# Hmi.net
KiCad netlist of a schematic drawn in Altium Designer
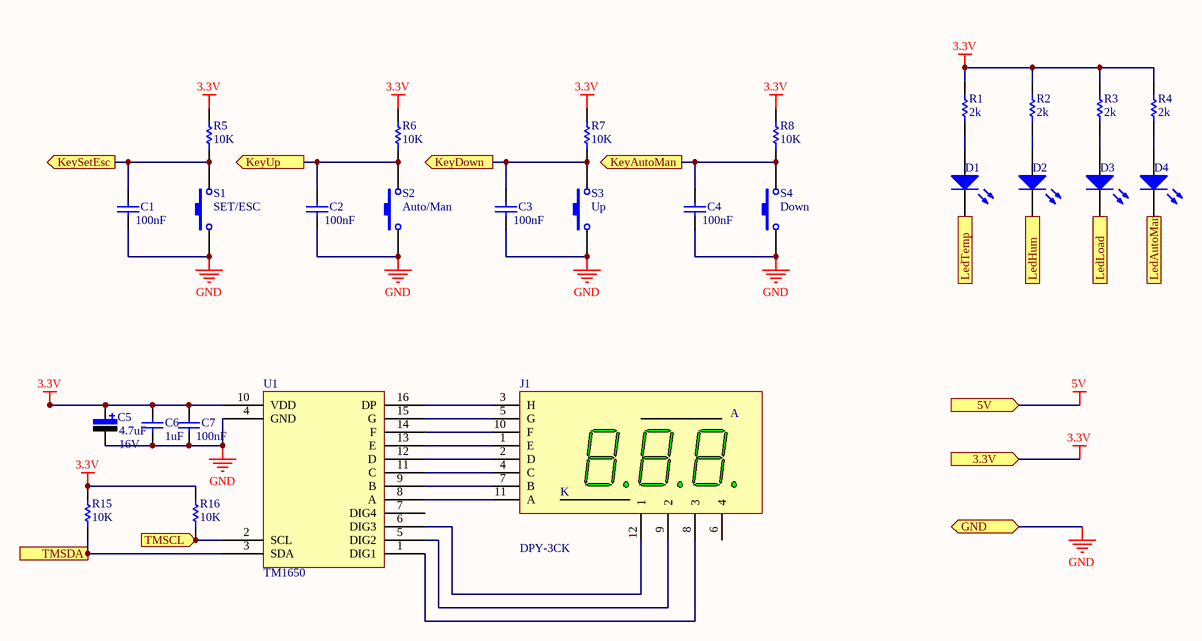
[diagram p0: Hmi.SchDoc]

(export (version "E")
  (design (tool "Eeschema 10.0.6"))
  (components
    (comp (ref "C1")
      (value "100nF (104) 10% 50V")
      (footprint "0603_C")
      (description "贴片电容")
      (fields (field (name "ALTIUM_UNNAMED_1") "100nF"))
      (libsource (lib "Miscellaneous Devices LC") (part "0603 100nF (104) 10% 50V"))
    )
    (comp (ref "C2")
      (value "100nF (104) 10% 50V")
      (footprint "0603_C")
      (description "贴片电容")
      (fields (field (name "ALTIUM_UNNAMED_1") "100nF"))
      (libsource (lib "Miscellaneous Devices LC") (part "0603 100nF (104) 10% 50V"))
    )
    (comp (ref "C3")
      (value "100nF (104) 10% 50V")
      (footprint "0603_C")
      (description "贴片电容")
      (fields (field (name "ALTIUM_UNNAMED_1") "100nF"))
      (libsource (lib "Miscellaneous Devices LC") (part "0603 100nF (104) 10% 50V"))
    )
    (comp (ref "C4")
      (value "100nF (104) 10% 50V")
      (footprint "0603_C")
      (description "贴片电容")
      (fields (field (name "ALTIUM_UNNAMED_1") "100nF"))
      (libsource (lib "Miscellaneous Devices LC") (part "0603 100nF (104) 10% 50V"))
    )
    (comp (ref "C5")
      (value "4.7uF")
      (footprint "CAP-1206")
      (description "4.7uF/16V钽电容")
      (fields
        (field (name "VOL") "16V")
        (field (name "Comment") "4.7uF/16V")
        (field (name "PUBLISHER") "Altium Limited")
      )
      (libsource (lib "fszhang") (part "Cap Pol"))
    )
    (comp (ref "C6")
      (value "1uF (105) 10% 50V")
      (footprint "0603_C")
      (description "贴片电容")
      (fields (field (name "ALTIUM_UNNAMED_1") "1uF"))
      (libsource (lib "Miscellaneous Devices LC") (part "0603 1uF (105) 10% 50V"))
    )
    (comp (ref "C7")
      (value "100nF (104) 10% 50V")
      (footprint "0603_C")
      (description "贴片电容")
      (fields (field (name "ALTIUM_UNNAMED_1") "100nF"))
      (libsource (lib "Miscellaneous Devices LC") (part "0603 100nF (104) 10% 50V"))
    )
    (comp (ref "D1")
      (value "LED")
      (footprint "LED(小)")
      (description "Typical INFRARED GaAs LED")
      (fields (field (name "PUBLISHER") "Altium Limited"))
      (libsource (lib "Miscellaneous Devices") (part "LED0"))
    )
    (comp (ref "D2")
      (value "LED")
      (footprint "LED(小)")
      (description "Typical INFRARED GaAs LED")
      (fields (field (name "PUBLISHER") "Altium Limited"))
      (libsource (lib "Miscellaneous Devices") (part "LED0"))
    )
    (comp (ref "D3")
      (value "LED")
      (footprint "LED(小)")
      (description "Typical INFRARED GaAs LED")
      (fields (field (name "PUBLISHER") "Altium Limited"))
      (libsource (lib "Miscellaneous Devices") (part "LED0"))
    )
    (comp (ref "D4")
      (value "LED")
      (footprint "LED(小)")
      (description "Typical INFRARED GaAs LED")
      (fields (field (name "PUBLISHER") "Altium Limited"))
      (libsource (lib "Miscellaneous Devices") (part "LED0"))
    )
    (comp (ref "J1")
      (value "DPY-3CK")
      (footprint "DYP-3BIT_2.8")
      (description "共阴3位数码管")
      (libsource (lib "PowerDisplay") (part "DPY-3CK_1"))
    )
    (comp (ref "R1")
      (value "2k")
      (footprint "0603_R")
      (description "2k/±10%")
      (libsource (lib "Free Documents") (part "RES1"))
    )
    (comp (ref "R2")
      (value "2k")
      (footprint "0603_R")
      (description "2k/±10%")
      (libsource (lib "Free Documents") (part "RES1"))
    )
    (comp (ref "R3")
      (value "2k")
      (footprint "0603_R")
      (description "2k/±10%")
      (libsource (lib "Free Documents") (part "RES1"))
    )
    (comp (ref "R4")
      (value "2k")
      (footprint "0603_R")
      (description "2k/±10%")
      (libsource (lib "Free Documents") (part "RES1"))
    )
    (comp (ref "R5")
      (value "10K")
      (footprint "0603_R")
      (description "10K/±10%")
      (libsource (lib "Free Documents") (part "RES1"))
    )
    (comp (ref "R6")
      (value "10K")
      (footprint "0603_R")
      (description "10K/±10%")
      (libsource (lib "Free Documents") (part "RES1"))
    )
    (comp (ref "R7")
      (value "10K")
      (footprint "0603_R")
      (description "10K/±10%")
      (libsource (lib "Free Documents") (part "RES1"))
    )
    (comp (ref "R8")
      (value "10K")
      (footprint "0603_R")
      (description "10K/±10%")
      (libsource (lib "Free Documents") (part "RES1"))
    )
    (comp (ref "R15")
      (value "10K")
      (footprint "0603_R")
      (description "10K/±10%")
      (libsource (lib "Free Documents") (part "RES1"))
    )
    (comp (ref "R16")
      (value "10K")
      (footprint "0603_R")
      (description "10K/±10%")
      (libsource (lib "Free Documents") (part "RES1"))
    )
    (comp (ref "S1")
      (value "SET/ESC")
      (footprint "Switch_4_6*6")
      (description "6*6*5四脚直插轻触开关")
      (libsource (lib "Free Documents") (part "SW-PB"))
    )
    (comp (ref "S2")
      (value "Auto/Man")
      (footprint "Switch_4_6*6")
      (description "6*6*5四脚直插轻触开关")
      (libsource (lib "Free Documents") (part "SW-PB"))
    )
    (comp (ref "S3")
      (value "Up")
      (footprint "Switch_4_6*6")
      (description "6*6*5四脚直插轻触开关")
      (libsource (lib "Free Documents") (part "SW-PB"))
    )
    (comp (ref "S4")
      (value "Down")
      (footprint "Switch_4_6*6")
      (description "6*6*5四脚直插轻触开关")
      (libsource (lib "Free Documents") (part "SW-PB"))
    )
    (comp (ref "U1")
      (value "TM1650")
      (footprint "Miscellaneous Devices LC:SOIC-16_150mil")
      (libsource (lib "LifeTestDevice") (part "TM1650"))
    )
  )
  (nets
    (net (code "1") (name "/KeyAutoMan") (class "Default")
      (node (ref "C4") (pin "2") (pinfunction "2_2") (pintype "passive"))
      (node (ref "R8") (pin "1") (pinfunction "1_1") (pintype "passive"))
      (node (ref "S4") (pin "2") (pinfunction "2_2") (pintype "passive"))
    )
    (net (code "2") (name "/KeyDown") (class "Default")
      (node (ref "C3") (pin "2") (pinfunction "2_2") (pintype "passive"))
      (node (ref "R7") (pin "1") (pinfunction "1_1") (pintype "passive"))
      (node (ref "S3") (pin "2") (pinfunction "2_2") (pintype "passive"))
    )
    (net (code "3") (name "/KeySetEsc") (class "Default")
      (node (ref "C1") (pin "2") (pinfunction "2_2") (pintype "passive"))
      (node (ref "R5") (pin "1") (pinfunction "1_1") (pintype "passive"))
      (node (ref "S1") (pin "2") (pinfunction "2_2") (pintype "passive"))
    )
    (net (code "4") (name "/KeyUp") (class "Default")
      (node (ref "C2") (pin "2") (pinfunction "2_2") (pintype "passive"))
      (node (ref "R6") (pin "1") (pinfunction "1_1") (pintype "passive"))
      (node (ref "S2") (pin "2") (pinfunction "2_2") (pintype "passive"))
    )
    (net (code "5") (name "/LedAutoMan") (class "Default")
      (node (ref "D4") (pin "2") (pinfunction "K_2") (pintype "passive"))
    )
    (net (code "6") (name "/LedHum") (class "Default")
      (node (ref "D2") (pin "2") (pinfunction "K_2") (pintype "passive"))
    )
    (net (code "7") (name "/LedLoad") (class "Default")
      (node (ref "D3") (pin "2") (pinfunction "K_2") (pintype "passive"))
    )
    (net (code "8") (name "/LedTemp") (class "Default")
      (node (ref "D1") (pin "2") (pinfunction "K_2") (pintype "passive"))
    )
    (net (code "9") (name "/TMSCL") (class "Default")
      (node (ref "R16") (pin "1") (pinfunction "1_1") (pintype "passive"))
      (node (ref "U1") (pin "2") (pinfunction "SCL_2") (pintype "passive"))
    )
    (net (code "10") (name "/TMSDA") (class "Default")
      (node (ref "R15") (pin "1") (pinfunction "1_1") (pintype "passive"))
      (node (ref "U1") (pin "3") (pinfunction "SDA_3") (pintype "passive"))
    )
    (net (code "11") (name "3.3V") (class "Default")
      (node (ref "C5") (pin "1") (pinfunction "1_1") (pintype "passive"))
      (node (ref "C6") (pin "2") (pinfunction "2_2") (pintype "passive"))
      (node (ref "C7") (pin "2") (pinfunction "2_2") (pintype "passive"))
      (node (ref "R1") (pin "1") (pinfunction "1_1") (pintype "passive"))
      (node (ref "R15") (pin "2") (pinfunction "2_2") (pintype "passive"))
      (node (ref "R16") (pin "2") (pinfunction "2_2") (pintype "passive"))
      (node (ref "R2") (pin "1") (pinfunction "1_1") (pintype "passive"))
      (node (ref "R3") (pin "1") (pinfunction "1_1") (pintype "passive"))
      (node (ref "R4") (pin "1") (pinfunction "1_1") (pintype "passive"))
      (node (ref "R5") (pin "2") (pinfunction "2_2") (pintype "passive"))
      (node (ref "R6") (pin "2") (pinfunction "2_2") (pintype "passive"))
      (node (ref "R7") (pin "2") (pinfunction "2_2") (pintype "passive"))
      (node (ref "R8") (pin "2") (pinfunction "2_2") (pintype "passive"))
      (node (ref "U1") (pin "10") (pinfunction "VDD_10") (pintype "passive"))
    )
    (net (code "13") (name "GND") (class "Default")
      (node (ref "C1") (pin "1") (pinfunction "1_1") (pintype "passive"))
      (node (ref "C2") (pin "1") (pinfunction "1_1") (pintype "passive"))
      (node (ref "C3") (pin "1") (pinfunction "1_1") (pintype "passive"))
      (node (ref "C4") (pin "1") (pinfunction "1_1") (pintype "passive"))
      (node (ref "C5") (pin "2") (pinfunction "2_2") (pintype "passive"))
      (node (ref "C6") (pin "1") (pinfunction "1_1") (pintype "passive"))
      (node (ref "C7") (pin "1") (pinfunction "1_1") (pintype "passive"))
      (node (ref "S1") (pin "1") (pinfunction "1_1") (pintype "passive"))
      (node (ref "S2") (pin "1") (pinfunction "1_1") (pintype "passive"))
      (node (ref "S3") (pin "1") (pinfunction "1_1") (pintype "passive"))
      (node (ref "S4") (pin "1") (pinfunction "1_1") (pintype "passive"))
      (node (ref "U1") (pin "4") (pinfunction "GND_4") (pintype "passive"))
    )
    (net (code "14") (name "Net-(D1-A)") (class "Default")
      (node (ref "D1") (pin "1") (pinfunction "A_1") (pintype "passive"))
      (node (ref "R1") (pin "2") (pinfunction "2_2") (pintype "passive"))
    )
    (net (code "15") (name "Net-(D2-A)") (class "Default")
      (node (ref "D2") (pin "1") (pinfunction "A_1") (pintype "passive"))
      (node (ref "R2") (pin "2") (pinfunction "2_2") (pintype "passive"))
    )
    (net (code "16") (name "Net-(D3-A)") (class "Default")
      (node (ref "D3") (pin "1") (pinfunction "A_1") (pintype "passive"))
      (node (ref "R3") (pin "2") (pinfunction "2_2") (pintype "passive"))
    )
    (net (code "17") (name "Net-(D4-A)") (class "Default")
      (node (ref "D4") (pin "1") (pinfunction "A_1") (pintype "passive"))
      (node (ref "R4") (pin "2") (pinfunction "2_2") (pintype "passive"))
    )
    (net (code "18") (name "Net-(J1-1)") (class "Default")
      (node (ref "J1") (pin "12") (pinfunction "1_12") (pintype "passive"))
      (node (ref "U1") (pin "6") (pinfunction "DIG3_6") (pintype "passive"))
    )
    (net (code "19") (name "Net-(J1-2)") (class "Default")
      (node (ref "J1") (pin "9") (pinfunction "2_9") (pintype "passive"))
      (node (ref "U1") (pin "5") (pinfunction "DIG2_5") (pintype "passive"))
    )
    (net (code "20") (name "Net-(J1-3)") (class "Default")
      (node (ref "J1") (pin "8") (pinfunction "3_8") (pintype "passive"))
      (node (ref "U1") (pin "1") (pinfunction "DIG1_1") (pintype "passive"))
    )
    (net (code "21") (name "Net-(J1-A)") (class "Default")
      (node (ref "J1") (pin "11") (pinfunction "A_11") (pintype "passive"))
      (node (ref "U1") (pin "8") (pinfunction "A_8") (pintype "passive"))
    )
    (net (code "22") (name "Net-(J1-B)") (class "Default")
      (node (ref "J1") (pin "7") (pinfunction "B_7") (pintype "passive"))
      (node (ref "U1") (pin "9") (pinfunction "B_9") (pintype "passive"))
    )
    (net (code "23") (name "Net-(J1-C)") (class "Default")
      (node (ref "J1") (pin "4") (pinfunction "C_4") (pintype "passive"))
      (node (ref "U1") (pin "11") (pinfunction "C_11") (pintype "passive"))
    )
    (net (code "24") (name "Net-(J1-D)") (class "Default")
      (node (ref "J1") (pin "2") (pinfunction "D_2") (pintype "passive"))
      (node (ref "U1") (pin "12") (pinfunction "D_12") (pintype "passive"))
    )
    (net (code "25") (name "Net-(J1-E)") (class "Default")
      (node (ref "J1") (pin "1") (pinfunction "E_1") (pintype "passive"))
      (node (ref "U1") (pin "13") (pinfunction "E_13") (pintype "passive"))
    )
    (net (code "26") (name "Net-(J1-F)") (class "Default")
      (node (ref "J1") (pin "10") (pinfunction "F_10") (pintype "passive"))
      (node (ref "U1") (pin "14") (pinfunction "F_14") (pintype "passive"))
    )
    (net (code "27") (name "Net-(J1-G)") (class "Default")
      (node (ref "J1") (pin "5") (pinfunction "G_5") (pintype "passive"))
      (node (ref "U1") (pin "15") (pinfunction "G_15") (pintype "passive"))
    )
    (net (code "28") (name "Net-(J1-H)") (class "Default")
      (node (ref "J1") (pin "3") (pinfunction "H_3") (pintype "passive"))
      (node (ref "U1") (pin "16") (pinfunction "DP_16") (pintype "passive"))
    )
    (net (code "29") (name "unconnected-(J1-4-Pad6)") (class "Default")
      (node (ref "J1") (pin "6") (pinfunction "4_6") (pintype "passive"))
    )
    (net (code "30") (name "unconnected-(U1-DIG4-Pad7)") (class "Default")
      (node (ref "U1") (pin "7") (pinfunction "DIG4_7") (pintype "passive"))
    )
  )
)
